# SL_LCD_SW_LED_2E.net
KiCad netlist of a schematic drawn in Altium Designer
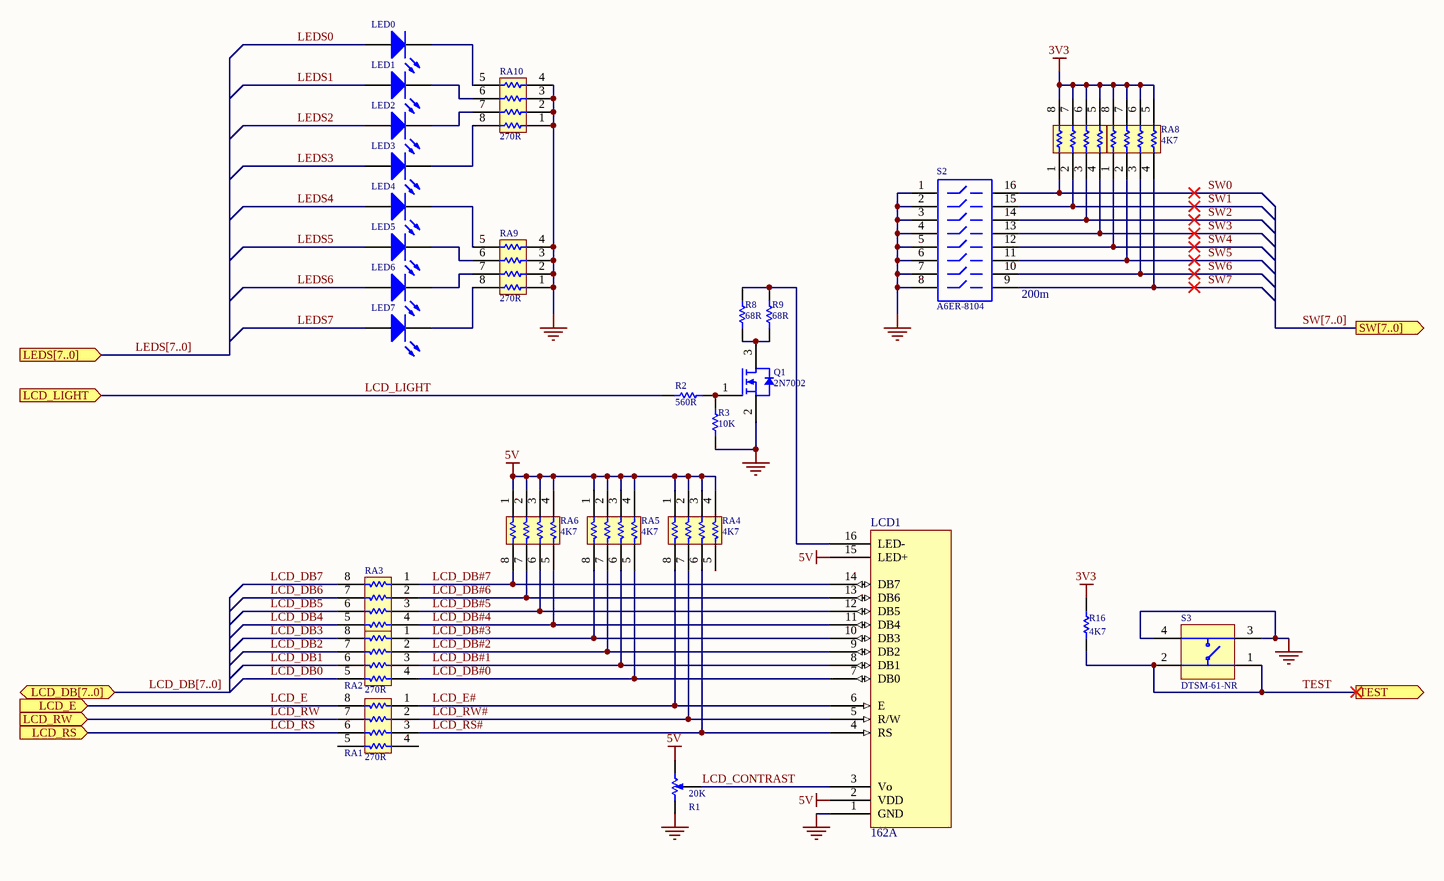
[diagram p0: SL_LCD_SW_LED_2E.SchDoc]

(export (version "E")
  (design (tool "Eeschema 10.0.6"))
  (components
    (comp (ref "LCD1")
      (value "162A")
      (footprint "Altium Nanoboard Project:162A")
      (description "16 char * 2 line LCD character display with b/light")
      (libsource (lib "Altium Nanoboard Project") (part "162A"))
    )
    (comp (ref "LED0")
      (value "HSMH-C170")
      (footprint "Altium Nanoboard Project:SMD _LED")
      (description "Typical RED GaAs SMD LED Agilent make")
      (libsource (lib "Altium Nanoboard Project") (part "HSMX-C670"))
    )
    (comp (ref "LED1")
      (value "HSMH-C170")
      (footprint "Altium Nanoboard Project:SMD _LED")
      (description "Typical RED GaAs SMD LED Agilent make")
      (libsource (lib "Altium Nanoboard Project") (part "HSMX-C670"))
    )
    (comp (ref "LED2")
      (value "HSMH-C170")
      (footprint "Altium Nanoboard Project:SMD _LED")
      (description "Typical RED GaAs SMD LED Agilent make")
      (libsource (lib "Altium Nanoboard Project") (part "HSMX-C670"))
    )
    (comp (ref "LED3")
      (value "HSMH-C170")
      (footprint "Altium Nanoboard Project:SMD _LED")
      (description "Typical RED GaAs SMD LED Agilent make")
      (libsource (lib "Altium Nanoboard Project") (part "HSMX-C670"))
    )
    (comp (ref "LED4")
      (value "HSMH-C170")
      (footprint "Altium Nanoboard Project:SMD _LED")
      (description "Typical RED GaAs SMD LED Agilent make")
      (libsource (lib "Altium Nanoboard Project") (part "HSMX-C670"))
    )
    (comp (ref "LED5")
      (value "HSMH-C170")
      (footprint "Altium Nanoboard Project:SMD _LED")
      (description "Typical RED GaAs SMD LED Agilent make")
      (libsource (lib "Altium Nanoboard Project") (part "HSMX-C670"))
    )
    (comp (ref "LED6")
      (value "HSMH-C170")
      (footprint "Altium Nanoboard Project:SMD _LED")
      (description "Typical RED GaAs SMD LED Agilent make")
      (libsource (lib "Altium Nanoboard Project") (part "HSMX-C670"))
    )
    (comp (ref "LED7")
      (value "HSMH-C170")
      (footprint "Altium Nanoboard Project:SMD _LED")
      (description "Typical RED GaAs SMD LED Agilent make")
      (libsource (lib "Altium Nanoboard Project") (part "HSMX-C670"))
    )
    (comp (ref "Q1")
      (value "2N7002")
      (footprint "Altium Nanoboard Project:SO-G3")
      (description "N Channel Mosfet")
      (libsource (lib "Altium Nanoboard Project") (part "2N7002"))
    )
    (comp (ref "R1")
      (value "20K")
      (footprint "POT4MM-2")
      (description "Square Trimming Potentiometer")
      (libsource (lib "Miscellaneous Devices") (part "RPot SM"))
    )
    (comp (ref "R2")
      (value "560R")
      (footprint "Altium Nanoboard Project:CC2012-0805")
      (description "Resistor")
      (libsource (lib "") (part "RES_1"))
    )
    (comp (ref "R3")
      (value "10K")
      (footprint "Altium Nanoboard Project:CC2012-0805")
      (description "Resistor")
      (libsource (lib "") (part "RES_1"))
    )
    (comp (ref "R8")
      (value "68R")
      (footprint "Altium Nanoboard Project:CC2012-0805")
      (description "Resistor")
      (libsource (lib "Altium Nanoboard Project") (part "RES"))
    )
    (comp (ref "R9")
      (value "68R")
      (footprint "Altium Nanoboard Project:CC2012-0805")
      (description "Resistor")
      (libsource (lib "Altium Nanoboard Project") (part "RES"))
    )
    (comp (ref "R16")
      (value "4K7")
      (footprint "Altium Nanoboard Project:CC2012-0805")
      (description "Resistor")
      (libsource (lib "") (part "RES_1"))
    )
    (comp (ref "RA1")
      (value "270R")
      (footprint "Altium Nanoboard Project:MNR34")
      (description "3216x4 Resistor Array")
      (libsource (lib "Altium Nanoboard Project") (part "MNR34"))
    )
    (comp (ref "RA2")
      (value "270R")
      (footprint "Altium Nanoboard Project:MNR34")
      (description "3216x4 Resistor Array")
      (libsource (lib "Altium Nanoboard Project") (part "MNR34"))
    )
    (comp (ref "RA3")
      (value "270R")
      (footprint "Altium Nanoboard Project:MNR34")
      (description "3216x4 Resistor Array")
      (libsource (lib "Altium Nanoboard Project") (part "MNR34"))
    )
    (comp (ref "RA4")
      (value "4K7")
      (footprint "MNR34T")
      (description "3216x4 Resistor Array")
      (libsource (lib "") (part "MNR34_1"))
    )
    (comp (ref "RA5")
      (value "4K7")
      (footprint "MNR34T")
      (description "3216x4 Resistor Array")
      (libsource (lib "") (part "MNR34_1"))
    )
    (comp (ref "RA6")
      (value "4K7")
      (footprint "MNR34T")
      (description "3216x4 Resistor Array")
      (libsource (lib "") (part "MNR34_1"))
    )
    (comp (ref "RA7")
      (value "4K7")
      (footprint "MNR34T")
      (description "3216x4 Resistor Array")
      (libsource (lib "") (part "MNR34_2"))
    )
    (comp (ref "RA8")
      (value "4K7")
      (footprint "MNR34T")
      (description "3216x4 Resistor Array")
      (libsource (lib "") (part "MNR34_2"))
    )
    (comp (ref "RA9")
      (value "270R")
      (footprint "MNR34T")
      (description "3216x4 Resistor Array")
      (libsource (lib "") (part "MNR34_3"))
    )
    (comp (ref "RA10")
      (value "270R")
      (footprint "MNR34T")
      (description "3216x4 Resistor Array")
      (libsource (lib "") (part "MNR34_3"))
    )
    (comp (ref "S2")
      (value "A6ER-8104")
      (footprint "Altium Nanoboard Project:DIP-16-KEY")
      (description "DIP Switch Side actuator long liver Piano Key")
      (fields (field (name "ALTIUM_VALUE") "200m"))
      (libsource (lib "Altium Nanoboard Project") (part "A6ER-8104"))
    )
    (comp (ref "S3")
      (value "DTSM-61-NR")
      (footprint "Altium Nanoboard Project:B3FS_SWITCH")
      (description "SPNA SMD Keyboard Switch")
      (libsource (lib "Altium Nanoboard Project") (part "B3FS"))
    )
  )
  (nets
    (net (code "1") (name "/LCD_CONTRAST") (class "Default")
      (node (ref "LCD1") (pin "3") (pinfunction "Vo_3") (pintype "tri_state"))
      (node (ref "R1") (pin "W") (pintype "passive"))
    )
    (net (code "2") (name "/LCD_DB#0") (class "Default")
      (node (ref "LCD1") (pin "7") (pinfunction "DB0_7") (pintype "bidirectional"))
      (node (ref "RA2") (pin "4") (pintype "passive"))
      (node (ref "RA5") (pin "5") (pintype "passive"))
    )
    (net (code "3") (name "/LCD_DB#1") (class "Default")
      (node (ref "LCD1") (pin "8") (pinfunction "DB1_8") (pintype "bidirectional"))
      (node (ref "RA2") (pin "3") (pintype "passive"))
      (node (ref "RA5") (pin "6") (pintype "passive"))
    )
    (net (code "4") (name "/LCD_DB#2") (class "Default")
      (node (ref "LCD1") (pin "9") (pinfunction "DB2_9") (pintype "bidirectional"))
      (node (ref "RA2") (pin "2") (pintype "passive"))
      (node (ref "RA5") (pin "7") (pintype "passive"))
    )
    (net (code "5") (name "/LCD_DB#3") (class "Default")
      (node (ref "LCD1") (pin "10") (pinfunction "DB3_10") (pintype "bidirectional"))
      (node (ref "RA2") (pin "1") (pintype "passive"))
      (node (ref "RA5") (pin "8") (pintype "passive"))
    )
    (net (code "6") (name "/LCD_DB#4") (class "Default")
      (node (ref "LCD1") (pin "11") (pinfunction "DB4_11") (pintype "bidirectional"))
      (node (ref "RA3") (pin "4") (pintype "passive"))
      (node (ref "RA6") (pin "5") (pintype "passive"))
    )
    (net (code "7") (name "/LCD_DB#5") (class "Default")
      (node (ref "LCD1") (pin "12") (pinfunction "DB5_12") (pintype "bidirectional"))
      (node (ref "RA3") (pin "3") (pintype "passive"))
      (node (ref "RA6") (pin "6") (pintype "passive"))
    )
    (net (code "8") (name "/LCD_DB#6") (class "Default")
      (node (ref "LCD1") (pin "13") (pinfunction "DB6_13") (pintype "bidirectional"))
      (node (ref "RA3") (pin "2") (pintype "passive"))
      (node (ref "RA6") (pin "7") (pintype "passive"))
    )
    (net (code "9") (name "/LCD_DB#7") (class "Default")
      (node (ref "LCD1") (pin "14") (pinfunction "DB7_14") (pintype "bidirectional"))
      (node (ref "RA3") (pin "1") (pintype "passive"))
      (node (ref "RA6") (pin "8") (pintype "passive"))
    )
    (net (code "10") (name "/LCD_DB0") (class "Default") (node (ref "RA2") (pin "5") (pintype "passive")))
    (net (code "11") (name "/LCD_DB1") (class "Default") (node (ref "RA2") (pin "6") (pintype "passive")))
    (net (code "12") (name "/LCD_DB2") (class "Default") (node (ref "RA2") (pin "7") (pintype "passive")))
    (net (code "13") (name "/LCD_DB3") (class "Default") (node (ref "RA2") (pin "8") (pintype "passive")))
    (net (code "14") (name "/LCD_DB4") (class "Default") (node (ref "RA3") (pin "5") (pintype "passive")))
    (net (code "15") (name "/LCD_DB5") (class "Default") (node (ref "RA3") (pin "6") (pintype "passive")))
    (net (code "16") (name "/LCD_DB6") (class "Default") (node (ref "RA3") (pin "7") (pintype "passive")))
    (net (code "17") (name "/LCD_DB7") (class "Default") (node (ref "RA3") (pin "8") (pintype "passive")))
    (net (code "19") (name "/LCD_E") (class "Default") (node (ref "RA1") (pin "8") (pintype "passive")))
    (net (code "20") (name "/LCD_E#") (class "Default")
      (node (ref "LCD1") (pin "6") (pinfunction "E_6") (pintype "input"))
      (node (ref "RA1") (pin "1") (pintype "passive"))
      (node (ref "RA4") (pin "8") (pintype "passive"))
    )
    (net (code "21") (name "/LCD_LIGHT") (class "Default")
      (node (ref "R2") (pin "1") (pinfunction "1_1") (pintype "passive"))
    )
    (net (code "22") (name "/LCD_RS") (class "Default") (node (ref "RA1") (pin "6") (pintype "passive")))
    (net (code "23") (name "/LCD_RS#") (class "Default")
      (node (ref "LCD1") (pin "4") (pinfunction "RS_4") (pintype "input"))
      (node (ref "RA1") (pin "3") (pintype "passive"))
      (node (ref "RA4") (pin "6") (pintype "passive"))
    )
    (net (code "24") (name "/LCD_RW") (class "Default") (node (ref "RA1") (pin "7") (pintype "passive")))
    (net (code "25") (name "/LCD_RW#") (class "Default")
      (node (ref "LCD1") (pin "5") (pinfunction "R/W_5") (pintype "input"))
      (node (ref "RA1") (pin "2") (pintype "passive"))
      (node (ref "RA4") (pin "7") (pintype "passive"))
    )
    (net (code "26") (name "/LEDS0") (class "Default")
      (node (ref "LED0") (pin "1") (pinfunction "A_1") (pintype "passive"))
    )
    (net (code "27") (name "/LEDS1") (class "Default")
      (node (ref "LED1") (pin "1") (pinfunction "A_1") (pintype "passive"))
    )
    (net (code "28") (name "/LEDS2") (class "Default")
      (node (ref "LED2") (pin "1") (pinfunction "A_1") (pintype "passive"))
    )
    (net (code "29") (name "/LEDS3") (class "Default")
      (node (ref "LED3") (pin "1") (pinfunction "A_1") (pintype "passive"))
    )
    (net (code "30") (name "/LEDS4") (class "Default")
      (node (ref "LED4") (pin "1") (pinfunction "A_1") (pintype "passive"))
    )
    (net (code "31") (name "/LEDS5") (class "Default")
      (node (ref "LED5") (pin "1") (pinfunction "A_1") (pintype "passive"))
    )
    (net (code "32") (name "/LEDS6") (class "Default")
      (node (ref "LED6") (pin "1") (pinfunction "A_1") (pintype "passive"))
    )
    (net (code "33") (name "/LEDS7") (class "Default")
      (node (ref "LED7") (pin "1") (pinfunction "A_1") (pintype "passive"))
    )
    (net (code "35") (name "/SW0") (class "Default")
      (node (ref "RA7") (pin "1") (pintype "passive"))
      (node (ref "S2") (pin "16") (pinfunction "16_16") (pintype "passive"))
    )
    (net (code "36") (name "/SW1") (class "Default")
      (node (ref "RA7") (pin "2") (pintype "passive"))
      (node (ref "S2") (pin "15") (pinfunction "15_15") (pintype "passive"))
    )
    (net (code "37") (name "/SW2") (class "Default")
      (node (ref "RA7") (pin "3") (pintype "passive"))
      (node (ref "S2") (pin "14") (pinfunction "14_14") (pintype "passive"))
    )
    (net (code "38") (name "/SW3") (class "Default")
      (node (ref "RA7") (pin "4") (pintype "passive"))
      (node (ref "S2") (pin "13") (pinfunction "13_13") (pintype "passive"))
    )
    (net (code "39") (name "/SW4") (class "Default")
      (node (ref "RA8") (pin "1") (pintype "passive"))
      (node (ref "S2") (pin "12") (pinfunction "12_12") (pintype "passive"))
    )
    (net (code "40") (name "/SW5") (class "Default")
      (node (ref "RA8") (pin "2") (pintype "passive"))
      (node (ref "S2") (pin "11") (pinfunction "11_11") (pintype "passive"))
    )
    (net (code "41") (name "/SW6") (class "Default")
      (node (ref "RA8") (pin "3") (pintype "passive"))
      (node (ref "S2") (pin "10") (pinfunction "10_10") (pintype "passive"))
    )
    (net (code "42") (name "/SW7") (class "Default")
      (node (ref "RA8") (pin "4") (pintype "passive"))
      (node (ref "S2") (pin "9") (pinfunction "9_9") (pintype "passive"))
    )
    (net (code "44") (name "/TEST") (class "Default")
      (node (ref "R16") (pin "2") (pinfunction "2_2") (pintype "passive"))
      (node (ref "S3") (pin "1") (pinfunction "1_1") (pintype "passive"))
      (node (ref "S3") (pin "2") (pinfunction "2_2") (pintype "passive"))
    )
    (net (code "45") (name "3V3") (class "Default")
      (node (ref "R16") (pin "1") (pinfunction "1_1") (pintype "passive"))
      (node (ref "RA7") (pin "5") (pintype "passive"))
      (node (ref "RA7") (pin "6") (pintype "passive"))
      (node (ref "RA7") (pin "7") (pintype "passive"))
      (node (ref "RA7") (pin "8") (pintype "passive"))
      (node (ref "RA8") (pin "5") (pintype "passive"))
      (node (ref "RA8") (pin "6") (pintype "passive"))
      (node (ref "RA8") (pin "7") (pintype "passive"))
      (node (ref "RA8") (pin "8") (pintype "passive"))
    )
    (net (code "46") (name "5V") (class "Default")
      (node (ref "LCD1") (pin "15") (pinfunction "LED+_15") (pintype "power_in"))
      (node (ref "LCD1") (pin "2") (pinfunction "VDD_2") (pintype "power_in"))
      (node (ref "R1") (pin "CW") (pinfunction "+_CW") (pintype "passive"))
      (node (ref "RA4") (pin "1") (pintype "passive"))
      (node (ref "RA4") (pin "2") (pintype "passive"))
      (node (ref "RA4") (pin "3") (pintype "passive"))
      (node (ref "RA4") (pin "4") (pintype "passive"))
      (node (ref "RA5") (pin "1") (pintype "passive"))
      (node (ref "RA5") (pin "2") (pintype "passive"))
      (node (ref "RA5") (pin "3") (pintype "passive"))
      (node (ref "RA5") (pin "4") (pintype "passive"))
      (node (ref "RA6") (pin "1") (pintype "passive"))
      (node (ref "RA6") (pin "2") (pintype "passive"))
      (node (ref "RA6") (pin "3") (pintype "passive"))
      (node (ref "RA6") (pin "4") (pintype "passive"))
    )
    (net (code "47") (name "GND") (class "Default")
      (node (ref "LCD1") (pin "1") (pinfunction "GND_1") (pintype "power_in"))
      (node (ref "Q1") (pin "2") (pintype "passive"))
      (node (ref "R1") (pin "CCW") (pinfunction "-_CCW") (pintype "passive"))
      (node (ref "R3") (pin "1") (pinfunction "1_1") (pintype "passive"))
      (node (ref "RA10") (pin "1") (pintype "passive"))
      (node (ref "RA10") (pin "2") (pintype "passive"))
      (node (ref "RA10") (pin "3") (pintype "passive"))
      (node (ref "RA10") (pin "4") (pintype "passive"))
      (node (ref "RA9") (pin "1") (pintype "passive"))
      (node (ref "RA9") (pin "2") (pintype "passive"))
      (node (ref "RA9") (pin "3") (pintype "passive"))
      (node (ref "RA9") (pin "4") (pintype "passive"))
      (node (ref "S2") (pin "1") (pinfunction "1_1") (pintype "passive"))
      (node (ref "S2") (pin "2") (pinfunction "2_2") (pintype "passive"))
      (node (ref "S2") (pin "3") (pinfunction "3_3") (pintype "passive"))
      (node (ref "S2") (pin "4") (pinfunction "4_4") (pintype "passive"))
      (node (ref "S2") (pin "5") (pinfunction "5_5") (pintype "passive"))
      (node (ref "S2") (pin "6") (pinfunction "6_6") (pintype "passive"))
      (node (ref "S2") (pin "7") (pinfunction "7_7") (pintype "passive"))
      (node (ref "S2") (pin "8") (pinfunction "8_8") (pintype "passive"))
      (node (ref "S3") (pin "3") (pinfunction "3_3") (pintype "passive"))
      (node (ref "S3") (pin "4") (pinfunction "4_4") (pintype "passive"))
    )
    (net (code "48") (name "Net-(LCD1-LED-)") (class "Default")
      (node (ref "LCD1") (pin "16") (pinfunction "LED-_16") (pintype "power_in"))
      (node (ref "R8") (pin "1") (pinfunction "1_1") (pintype "passive"))
      (node (ref "R9") (pin "1") (pinfunction "1_1") (pintype "passive"))
    )
    (net (code "49") (name "Net-(LED0-K)") (class "Default")
      (node (ref "LED0") (pin "2") (pinfunction "K_2") (pintype "passive"))
      (node (ref "RA10") (pin "5") (pintype "passive"))
    )
    (net (code "50") (name "Net-(LED1-K)") (class "Default")
      (node (ref "LED1") (pin "2") (pinfunction "K_2") (pintype "passive"))
      (node (ref "RA10") (pin "6") (pintype "passive"))
    )
    (net (code "51") (name "Net-(LED2-K)") (class "Default")
      (node (ref "LED2") (pin "2") (pinfunction "K_2") (pintype "passive"))
      (node (ref "RA10") (pin "7") (pintype "passive"))
    )
    (net (code "52") (name "Net-(LED3-K)") (class "Default")
      (node (ref "LED3") (pin "2") (pinfunction "K_2") (pintype "passive"))
      (node (ref "RA10") (pin "8") (pintype "passive"))
    )
    (net (code "53") (name "Net-(LED4-K)") (class "Default")
      (node (ref "LED4") (pin "2") (pinfunction "K_2") (pintype "passive"))
      (node (ref "RA9") (pin "5") (pintype "passive"))
    )
    (net (code "54") (name "Net-(LED5-K)") (class "Default")
      (node (ref "LED5") (pin "2") (pinfunction "K_2") (pintype "passive"))
      (node (ref "RA9") (pin "6") (pintype "passive"))
    )
    (net (code "55") (name "Net-(LED6-K)") (class "Default")
      (node (ref "LED6") (pin "2") (pinfunction "K_2") (pintype "passive"))
      (node (ref "RA9") (pin "7") (pintype "passive"))
    )
    (net (code "56") (name "Net-(LED7-K)") (class "Default")
      (node (ref "LED7") (pin "2") (pinfunction "K_2") (pintype "passive"))
      (node (ref "RA9") (pin "8") (pintype "passive"))
    )
    (net (code "57") (name "Net-(Q1-Pad1)") (class "Default")
      (node (ref "Q1") (pin "1") (pintype "passive"))
      (node (ref "R2") (pin "2") (pinfunction "2_2") (pintype "passive"))
      (node (ref "R3") (pin "2") (pinfunction "2_2") (pintype "passive"))
    )
    (net (code "58") (name "Net-(Q1-Pad3)") (class "Default")
      (node (ref "Q1") (pin "3") (pintype "passive"))
      (node (ref "R8") (pin "2") (pinfunction "2_2") (pintype "passive"))
      (node (ref "R9") (pin "2") (pinfunction "2_2") (pintype "passive"))
    )
    (net (code "59") (name "unconnected-(RA1-Pad4)") (class "Default")
      (node (ref "RA1") (pin "4") (pintype "passive"))
    )
    (net (code "60") (name "unconnected-(RA1-Pad5)") (class "Default")
      (node (ref "RA1") (pin "5") (pintype "passive"))
    )
    (net (code "61") (name "unconnected-(RA4-Pad5)") (class "Default")
      (node (ref "RA4") (pin "5") (pintype "passive"))
    )
  )
)
